# iF11K.net
KiCad netlist of a schematic drawn in Altium Designer
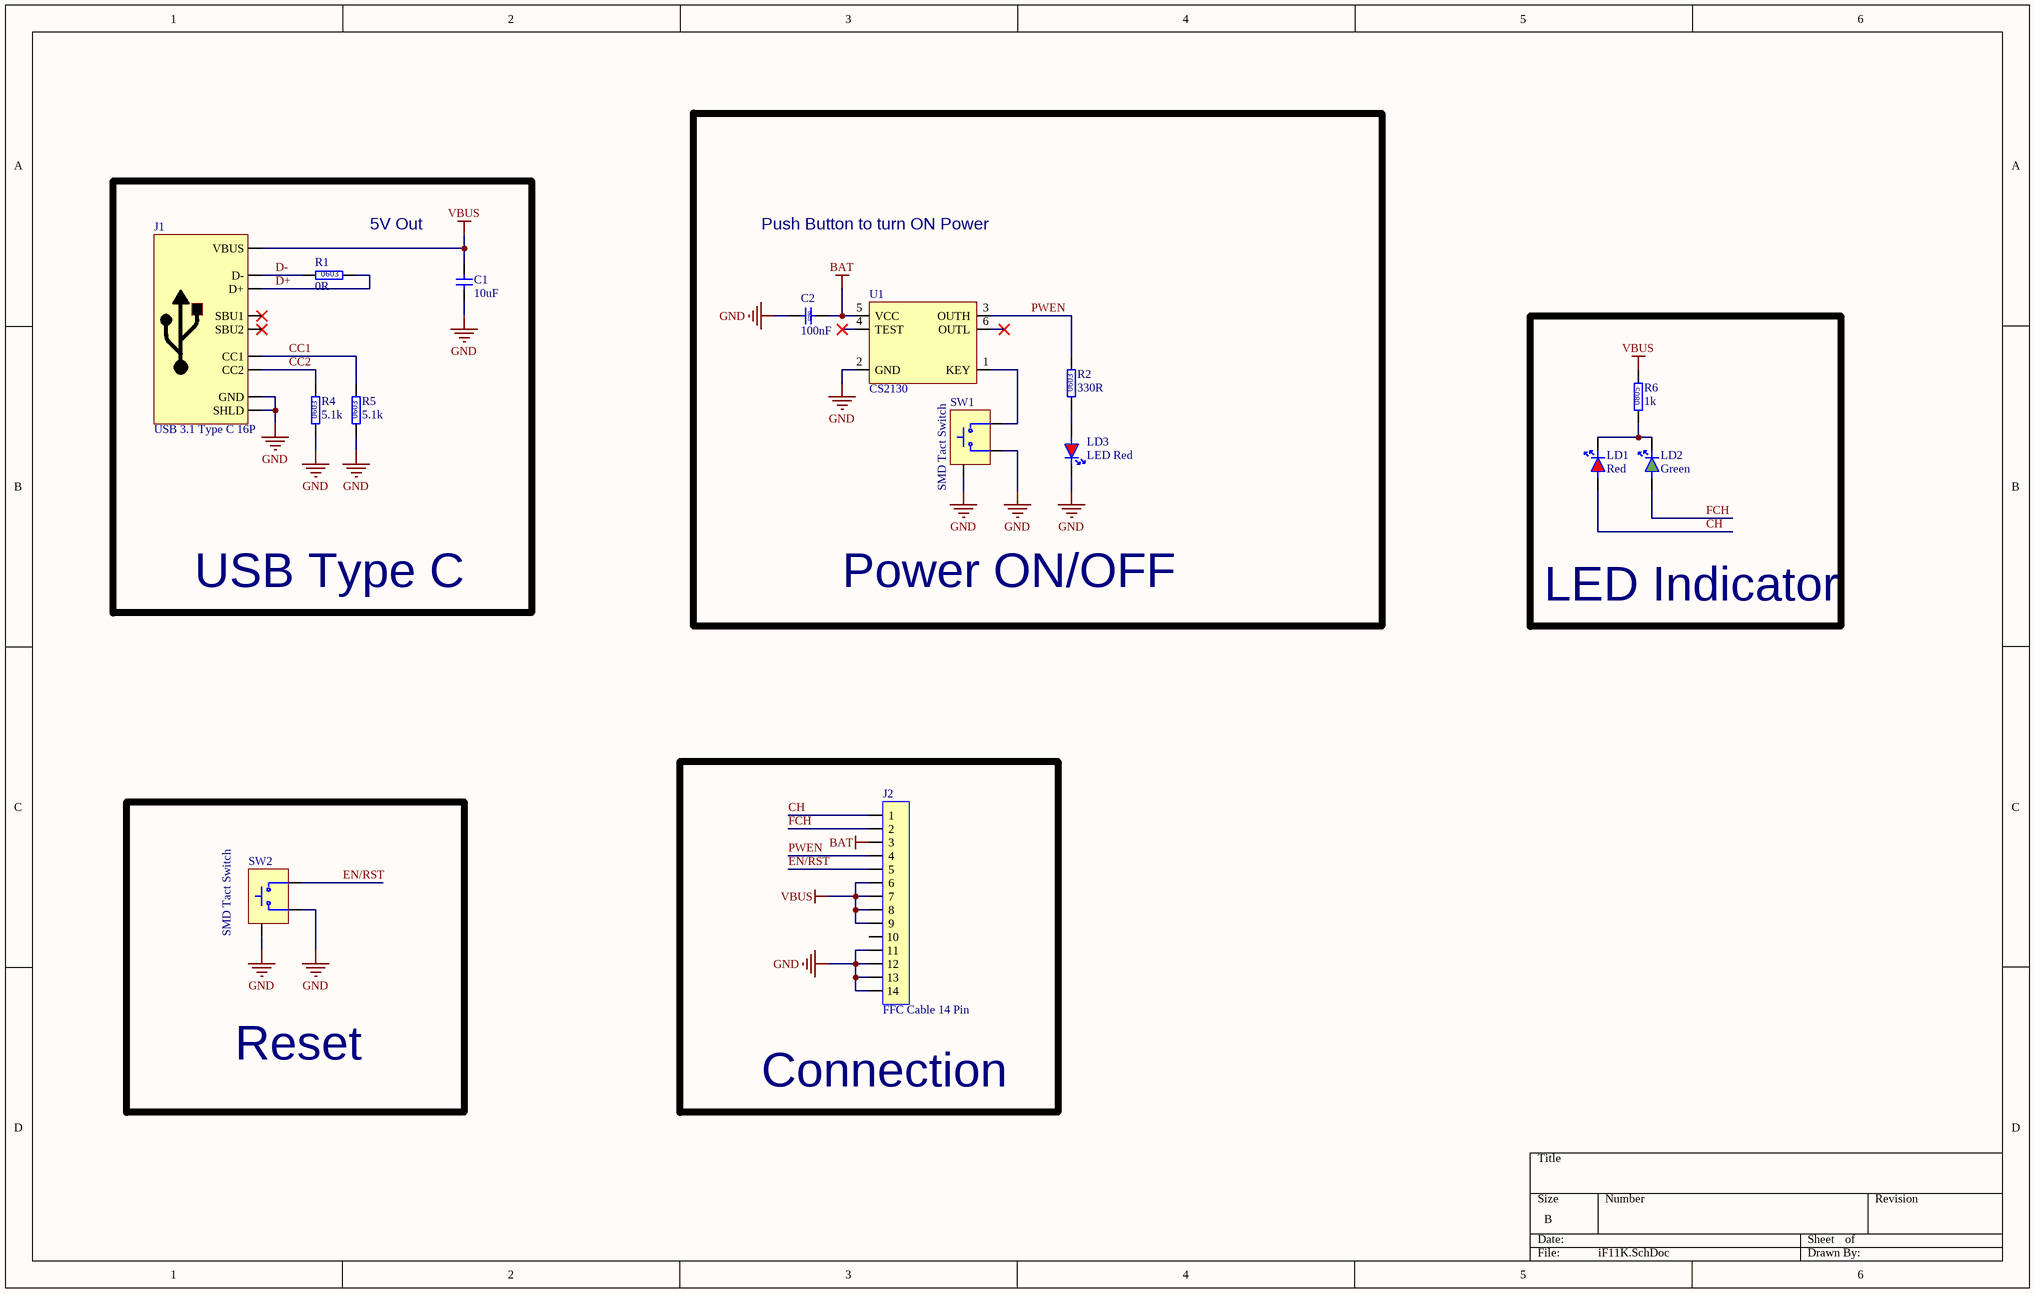
[diagram p0: iF11K.SchDoc]

(export (version "E")
  (design (tool "Eeschema 10.0.6"))
  (components
    (comp (ref "C1")
      (value "10uF")
      (footprint "C0603")
      (description "0603 Package 25V")
      (libsource (lib "Capacitors") (part "Capacitor"))
    )
    (comp (ref "C2")
      (value "100nF")
      (footprint "C0603")
      (description "10% 50V")
      (fields (field (name "PART NO") "W-T-CA-X703N100K50VNT") (field (name "MANUFACTURER") "FENGHUA"))
      (libsource (lib "Rescap") (part "C 0603 100nF 50V"))
    )
    (comp (ref "J1")
      (value "USB 3.1 Type C 16P")
      (footprint "USBC-16P -Upd")
      (description "TYPE-C 16PIN L8.35")
      (fields (field (name "PART NO") "W-T-CN-TYPE-C 16P"))
      (libsource (lib "Connector") (part "USB-C-16P"))
    )
    (comp (ref "J2")
      (value "FFC Cable 14 Pin")
      (footprint "FFC-14-1.25mm")
      (libsource (lib "Connector") (part "FFC14P"))
    )
    (comp (ref "LD1")
      (value "Red")
      (footprint "LED-0603-RED")
      (libsource (lib "Optoelectronics") (part "LED Red"))
    )
    (comp (ref "LD2")
      (value "Green")
      (footprint "LED-0603-GREEN")
      (libsource (lib "Optoelectronics") (part "LED Green"))
    )
    (comp (ref "LD3")
      (value "LED Red")
      (footprint "LED-0603-RED")
      (libsource (lib "Optoelectronics") (part "LED Red"))
    )
    (comp (ref "R1")
      (value "0R")
      (footprint "R0603-LD")
      (description "5%")
      (fields (field (name "PART NO") "W-T-RE-RS03K0RJT") (field (name "MANUFACTURER") "贴片"))
      (libsource (lib "Rescap") (part "R 0603 0R"))
    )
    (comp (ref "R2")
      (value "330R")
      (footprint "R0603-LD")
      (description "5%")
      (fields (field (name "PART NO") "W-T-RE-RS03K331JT"))
      (libsource (lib "Rescap") (part "R 0603 330R"))
    )
    (comp (ref "R4")
      (value "5.1k")
      (footprint "R0603-LD")
      (description "5%")
      (fields (field (name "PART NO") "W-T-RE-RS03K512JT"))
      (libsource (lib "Rescap") (part "R 0603 5.1k"))
    )
    (comp (ref "R5")
      (value "5.1k")
      (footprint "R0603-LD")
      (description "5%")
      (fields (field (name "PART NO") "W-T-RE-RS03K512JT"))
      (libsource (lib "Rescap") (part "R 0603 5.1k"))
    )
    (comp (ref "R6")
      (value "1k")
      (footprint "R0805-LD")
      (description "5%")
      (fields (field (name "PART NO") "W-T-RE-RS05K121JT"))
      (libsource (lib "Rescap") (part "R 0805 1k"))
    )
    (comp (ref "SW1")
      (value "SMD Tact Switch")
      (footprint "Light button")
      (libsource (lib "Switch") (part "soft tact switch"))
    )
    (comp (ref "SW2")
      (value "SMD Tact Switch")
      (footprint "Light button")
      (libsource (lib "Switch") (part "soft tact switch"))
    )
    (comp (ref "U1")
      (value "CS2130")
      (footprint "SOT23-6")
      (description "Single-button switch IC")
      (libsource (lib "mylib2") (part "CS2130"))
    )
  )
  (nets
    (net (code "1") (name "/CC1") (class "Default")
      (node (ref "J1") (pin "4") (pinfunction "CC1_4") (pintype "passive"))
      (node (ref "R5") (pin "2") (pinfunction "2_2") (pintype "passive"))
    )
    (net (code "2") (name "/CC2") (class "Default")
      (node (ref "J1") (pin "8") (pinfunction "CC2_8") (pintype "passive"))
      (node (ref "R4") (pin "2") (pinfunction "2_2") (pintype "passive"))
    )
    (net (code "3") (name "/CH") (class "Default")
      (node (ref "J2") (pin "1") (pinfunction "1_1") (pintype "passive"))
      (node (ref "LD1") (pin "1") (pinfunction "A_1") (pintype "passive"))
    )
    (net (code "4") (name "/D+") (class "Default")
      (node (ref "J1") (pin "6") (pinfunction "D+_6") (pintype "passive"))
      (node (ref "R1") (pin "2") (pinfunction "2_2") (pintype "passive"))
    )
    (net (code "5") (name "/D-") (class "Default")
      (node (ref "J1") (pin "5") (pinfunction "D-_5") (pintype "passive"))
      (node (ref "R1") (pin "1") (pinfunction "1_1") (pintype "passive"))
    )
    (net (code "6") (name "/EN{slash}RST") (class "Default")
      (node (ref "J2") (pin "5") (pinfunction "5_5") (pintype "passive"))
      (node (ref "SW2") (pin "2") (pinfunction "2_2") (pintype "passive"))
    )
    (net (code "7") (name "/FCH") (class "Default")
      (node (ref "J2") (pin "2") (pinfunction "2_2") (pintype "passive"))
      (node (ref "LD2") (pin "1") (pinfunction "A_1") (pintype "passive"))
    )
    (net (code "8") (name "/PWEN") (class "Default")
      (node (ref "J2") (pin "4") (pinfunction "4_4") (pintype "passive"))
      (node (ref "R2") (pin "2") (pinfunction "2_2") (pintype "passive"))
      (node (ref "U1") (pin "3") (pinfunction "OUTH_3") (pintype "passive"))
    )
    (net (code "9") (name "BAT") (class "Default")
      (node (ref "C2") (pin "1") (pinfunction "1_1") (pintype "passive"))
      (node (ref "J2") (pin "3") (pinfunction "3_3") (pintype "passive"))
      (node (ref "U1") (pin "5") (pinfunction "VCC_5") (pintype "passive"))
    )
    (net (code "10") (name "GND") (class "Default")
      (node (ref "C1") (pin "1") (pinfunction "1_1") (pintype "passive"))
      (node (ref "C2") (pin "2") (pinfunction "2_2") (pintype "passive"))
      (node (ref "J1") (pin "1") (pinfunction "GND_1") (pintype "passive"))
      (node (ref "J1") (pin "10") (pinfunction "SHLD_10") (pintype "passive"))
      (node (ref "J2") (pin "11") (pinfunction "11_11") (pintype "passive"))
      (node (ref "J2") (pin "12") (pinfunction "12_12") (pintype "passive"))
      (node (ref "J2") (pin "13") (pinfunction "13_13") (pintype "passive"))
      (node (ref "J2") (pin "14") (pinfunction "14_14") (pintype "passive"))
      (node (ref "LD3") (pin "2") (pinfunction "K_2") (pintype "passive"))
      (node (ref "R4") (pin "1") (pinfunction "1_1") (pintype "passive"))
      (node (ref "R5") (pin "1") (pinfunction "1_1") (pintype "passive"))
      (node (ref "SW1") (pin "1") (pinfunction "1_1") (pintype "passive"))
      (node (ref "SW1") (pin "3") (pinfunction "3_3") (pintype "passive"))
      (node (ref "SW2") (pin "1") (pinfunction "1_1") (pintype "passive"))
      (node (ref "SW2") (pin "3") (pinfunction "3_3") (pintype "passive"))
      (node (ref "U1") (pin "2") (pinfunction "GND_2") (pintype "passive"))
    )
    (net (code "11") (name "Net-(LD1-K)") (class "Default")
      (node (ref "LD1") (pin "2") (pinfunction "K_2") (pintype "passive"))
      (node (ref "LD2") (pin "2") (pinfunction "K_2") (pintype "passive"))
      (node (ref "R6") (pin "1") (pinfunction "1_1") (pintype "passive"))
    )
    (net (code "12") (name "Net-(LD3-A)") (class "Default")
      (node (ref "LD3") (pin "1") (pinfunction "A_1") (pintype "passive"))
      (node (ref "R2") (pin "1") (pinfunction "1_1") (pintype "passive"))
    )
    (net (code "13") (name "Net-(U1-KEY)") (class "Default")
      (node (ref "SW1") (pin "2") (pinfunction "2_2") (pintype "passive"))
      (node (ref "U1") (pin "1") (pinfunction "KEY_1") (pintype "passive"))
    )
    (net (code "14") (name "VBUS") (class "Default")
      (node (ref "C1") (pin "2") (pinfunction "2_2") (pintype "passive"))
      (node (ref "J1") (pin "2") (pinfunction "VBUS_2") (pintype "passive"))
      (node (ref "J2") (pin "6") (pinfunction "6_6") (pintype "passive"))
      (node (ref "J2") (pin "7") (pinfunction "7_7") (pintype "passive"))
      (node (ref "J2") (pin "8") (pinfunction "8_8") (pintype "passive"))
      (node (ref "J2") (pin "9") (pinfunction "9_9") (pintype "passive"))
      (node (ref "R6") (pin "2") (pinfunction "2_2") (pintype "passive"))
    )
    (net (code "15") (name "unconnected-(J1-SBU1-Pad7)") (class "Default")
      (node (ref "J1") (pin "7") (pinfunction "SBU1_7") (pintype "passive+no_connect"))
    )
    (net (code "16") (name "unconnected-(J1-SBU2-Pad3)") (class "Default")
      (node (ref "J1") (pin "3") (pinfunction "SBU2_3") (pintype "passive+no_connect"))
    )
    (net (code "17") (name "unconnected-(J2-Pad10)") (class "Default")
      (node (ref "J2") (pin "10") (pinfunction "10_10") (pintype "passive"))
    )
    (net (code "18") (name "unconnected-(U1-OUTL-Pad6)") (class "Default")
      (node (ref "U1") (pin "6") (pinfunction "OUTL_6") (pintype "passive+no_connect"))
    )
    (net (code "19") (name "unconnected-(U1-TEST-Pad4)") (class "Default")
      (node (ref "U1") (pin "4") (pinfunction "TEST_4") (pintype "passive+no_connect"))
    )
  )
)
